# BlueTooth_BM20_Breakout.net
KiCad netlist of a schematic drawn in EAGLE
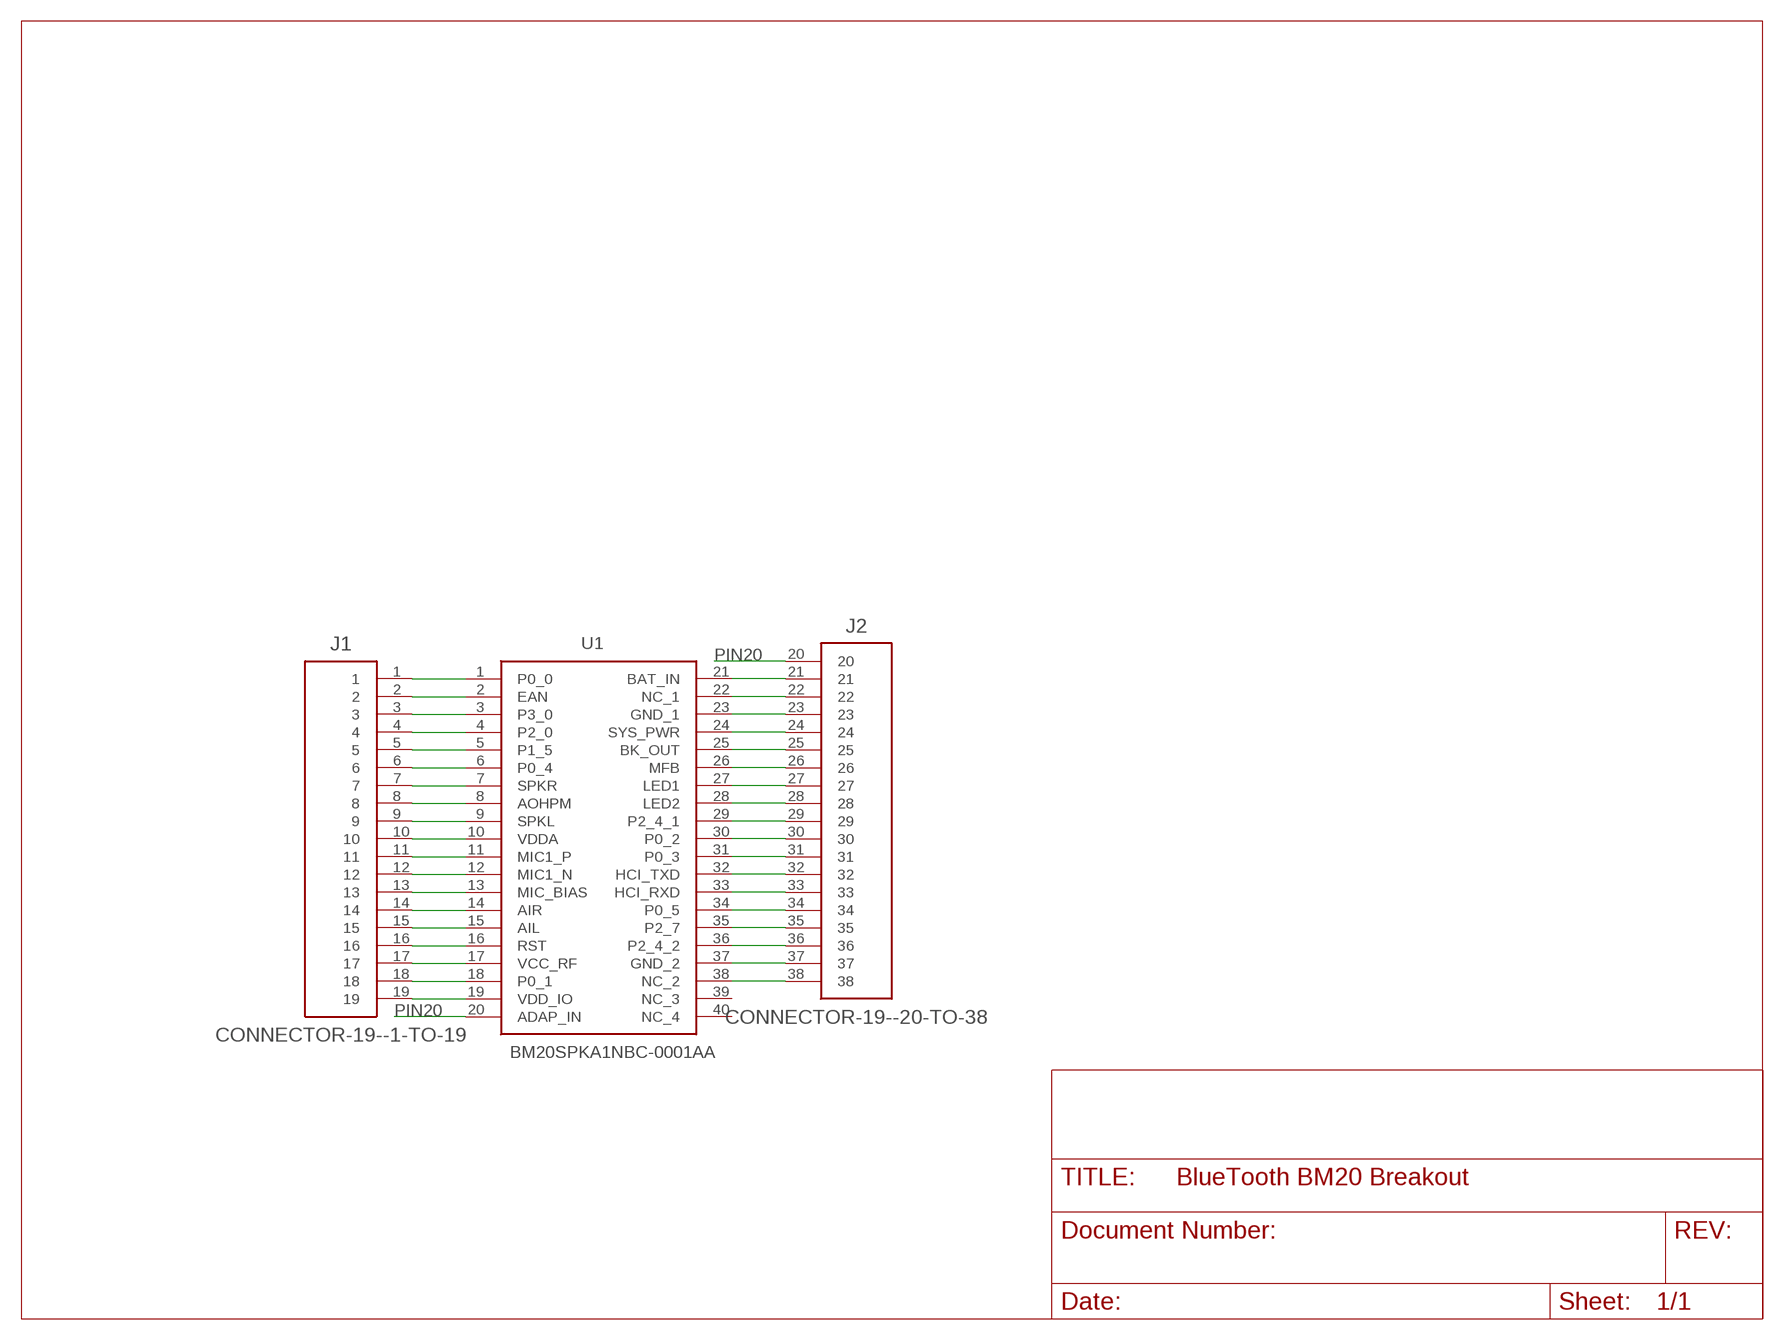
[diagram p0: schematic, sheet 1]

(export (version "E")
  (design (tool "Eeschema 10.0.6"))
  (components
    (comp (ref "J1")
      (value "CONNECTOR-19--1-TO-19")
      (footprint "eagle-import:ESQ-119-XX-XX-S")
      (libsource (lib "eagle-import") (part "CONNECTOR-19--1-TO-19"))
    )
    (comp (ref "J2")
      (value "CONNECTOR-19--20-TO-38")
      (footprint "eagle-import:ESQ-119-XX-XX-S--PIN-1-ROUND")
      (libsource (lib "eagle-import") (part "CONNECTOR-19--20-TO-38"))
    )
    (comp (ref "U1")
      (value "BM20SPKA1NBC-0001AA")
      (footprint "eagle-import:BM20SPKA1NBC0001AA")
      (fields (field (name "MOUSER_PART_NUMBER") "579-SPKA1NBC-0001AA"))
      (libsource (lib "eagle-import") (part "BM20SPKA1NBC-0001AA"))
    )
  )
  (nets
    (net (code "1") (name "/PIN20") (class "Default")
      (node (ref "J2") (pin "20") (pinfunction "20_20") (pintype "bidirectional"))
      (node (ref "U1") (pin "20") (pinfunction "ADAP_IN_20") (pintype "bidirectional"))
    )
    (net (code "2") (name "Net-(U1-AIL)") (class "Default")
      (node (ref "J1") (pin "15") (pinfunction "15_15") (pintype "bidirectional"))
      (node (ref "U1") (pin "15") (pinfunction "AIL_15") (pintype "bidirectional"))
    )
    (net (code "3") (name "Net-(U1-AIR)") (class "Default")
      (node (ref "J1") (pin "14") (pinfunction "14_14") (pintype "bidirectional"))
      (node (ref "U1") (pin "14") (pinfunction "AIR_14") (pintype "bidirectional"))
    )
    (net (code "4") (name "Net-(U1-AOHPM)") (class "Default")
      (node (ref "J1") (pin "8") (pinfunction "8_8") (pintype "bidirectional"))
      (node (ref "U1") (pin "8") (pinfunction "AOHPM_8") (pintype "bidirectional"))
    )
    (net (code "5") (name "Net-(U1-BAT_IN)") (class "Default")
      (node (ref "J2") (pin "21") (pinfunction "21_21") (pintype "bidirectional"))
      (node (ref "U1") (pin "21") (pinfunction "BAT_IN_21") (pintype "bidirectional"))
    )
    (net (code "6") (name "Net-(U1-BK_OUT)") (class "Default")
      (node (ref "J2") (pin "25") (pinfunction "25_25") (pintype "bidirectional"))
      (node (ref "U1") (pin "25") (pinfunction "BK_OUT_25") (pintype "bidirectional"))
    )
    (net (code "7") (name "Net-(U1-EAN)") (class "Default")
      (node (ref "J1") (pin "2") (pinfunction "2_2") (pintype "bidirectional"))
      (node (ref "U1") (pin "2") (pinfunction "EAN_2") (pintype "bidirectional"))
    )
    (net (code "8") (name "Net-(U1-GND_1)") (class "Default")
      (node (ref "J2") (pin "23") (pinfunction "23_23") (pintype "bidirectional"))
      (node (ref "U1") (pin "23") (pinfunction "GND_1_23") (pintype "bidirectional"))
    )
    (net (code "9") (name "Net-(U1-GND_2)") (class "Default")
      (node (ref "J2") (pin "37") (pinfunction "37_37") (pintype "bidirectional"))
      (node (ref "U1") (pin "37") (pinfunction "GND_2_37") (pintype "bidirectional"))
    )
    (net (code "10") (name "Net-(U1-HCI_RXD)") (class "Default")
      (node (ref "J2") (pin "33") (pinfunction "33_33") (pintype "bidirectional"))
      (node (ref "U1") (pin "33") (pinfunction "HCI_RXD_33") (pintype "bidirectional"))
    )
    (net (code "11") (name "Net-(U1-HCI_TXD)") (class "Default")
      (node (ref "J2") (pin "32") (pinfunction "32_32") (pintype "bidirectional"))
      (node (ref "U1") (pin "32") (pinfunction "HCI_TXD_32") (pintype "bidirectional"))
    )
    (net (code "12") (name "Net-(U1-LED1)") (class "Default")
      (node (ref "J2") (pin "27") (pinfunction "27_27") (pintype "bidirectional"))
      (node (ref "U1") (pin "27") (pinfunction "LED1_27") (pintype "bidirectional"))
    )
    (net (code "13") (name "Net-(U1-LED2)") (class "Default")
      (node (ref "J2") (pin "28") (pinfunction "28_28") (pintype "bidirectional"))
      (node (ref "U1") (pin "28") (pinfunction "LED2_28") (pintype "bidirectional"))
    )
    (net (code "14") (name "Net-(U1-MFB)") (class "Default")
      (node (ref "J2") (pin "26") (pinfunction "26_26") (pintype "bidirectional"))
      (node (ref "U1") (pin "26") (pinfunction "MFB_26") (pintype "bidirectional"))
    )
    (net (code "15") (name "Net-(U1-MIC1_N)") (class "Default")
      (node (ref "J1") (pin "12") (pinfunction "12_12") (pintype "bidirectional"))
      (node (ref "U1") (pin "12") (pinfunction "MIC1_N_12") (pintype "bidirectional"))
    )
    (net (code "16") (name "Net-(U1-MIC1_P)") (class "Default")
      (node (ref "J1") (pin "11") (pinfunction "11_11") (pintype "bidirectional"))
      (node (ref "U1") (pin "11") (pinfunction "MIC1_P_11") (pintype "bidirectional"))
    )
    (net (code "17") (name "Net-(U1-MIC_BIAS)") (class "Default")
      (node (ref "J1") (pin "13") (pinfunction "13_13") (pintype "bidirectional"))
      (node (ref "U1") (pin "13") (pinfunction "MIC_BIAS_13") (pintype "bidirectional"))
    )
    (net (code "18") (name "Net-(U1-NC_1)") (class "Default")
      (node (ref "J2") (pin "22") (pinfunction "22_22") (pintype "bidirectional"))
      (node (ref "U1") (pin "22") (pinfunction "NC_1_22") (pintype "bidirectional"))
    )
    (net (code "19") (name "Net-(U1-NC_2)") (class "Default")
      (node (ref "J2") (pin "38") (pinfunction "38_38") (pintype "bidirectional"))
      (node (ref "U1") (pin "38") (pinfunction "NC_2_38") (pintype "bidirectional"))
    )
    (net (code "20") (name "Net-(U1-P0_0)") (class "Default")
      (node (ref "J1") (pin "1") (pinfunction "1_1") (pintype "bidirectional"))
      (node (ref "U1") (pin "1") (pinfunction "P0_0_1") (pintype "bidirectional"))
    )
    (net (code "21") (name "Net-(U1-P0_1)") (class "Default")
      (node (ref "J1") (pin "18") (pinfunction "18_18") (pintype "bidirectional"))
      (node (ref "U1") (pin "18") (pinfunction "P0_1_18") (pintype "bidirectional"))
    )
    (net (code "22") (name "Net-(U1-P0_2)") (class "Default")
      (node (ref "J2") (pin "30") (pinfunction "30_30") (pintype "bidirectional"))
      (node (ref "U1") (pin "30") (pinfunction "P0_2_30") (pintype "bidirectional"))
    )
    (net (code "23") (name "Net-(U1-P0_3)") (class "Default")
      (node (ref "J2") (pin "31") (pinfunction "31_31") (pintype "bidirectional"))
      (node (ref "U1") (pin "31") (pinfunction "P0_3_31") (pintype "bidirectional"))
    )
    (net (code "24") (name "Net-(U1-P0_4)") (class "Default")
      (node (ref "J1") (pin "6") (pinfunction "6_6") (pintype "bidirectional"))
      (node (ref "U1") (pin "6") (pinfunction "P0_4_6") (pintype "bidirectional"))
    )
    (net (code "25") (name "Net-(U1-P0_5)") (class "Default")
      (node (ref "J2") (pin "34") (pinfunction "34_34") (pintype "bidirectional"))
      (node (ref "U1") (pin "34") (pinfunction "P0_5_34") (pintype "bidirectional"))
    )
    (net (code "26") (name "Net-(U1-P1_5)") (class "Default")
      (node (ref "J1") (pin "5") (pinfunction "5_5") (pintype "bidirectional"))
      (node (ref "U1") (pin "5") (pinfunction "P1_5_5") (pintype "bidirectional"))
    )
    (net (code "27") (name "Net-(U1-P2_0)") (class "Default")
      (node (ref "J1") (pin "4") (pinfunction "4_4") (pintype "bidirectional"))
      (node (ref "U1") (pin "4") (pinfunction "P2_0_4") (pintype "bidirectional"))
    )
    (net (code "28") (name "Net-(U1-P2_4_1)") (class "Default")
      (node (ref "J2") (pin "29") (pinfunction "29_29") (pintype "bidirectional"))
      (node (ref "U1") (pin "29") (pinfunction "P2_4_1_29") (pintype "bidirectional"))
    )
    (net (code "29") (name "Net-(U1-P2_4_2)") (class "Default")
      (node (ref "J2") (pin "36") (pinfunction "36_36") (pintype "bidirectional"))
      (node (ref "U1") (pin "36") (pinfunction "P2_4_2_36") (pintype "bidirectional"))
    )
    (net (code "30") (name "Net-(U1-P2_7)") (class "Default")
      (node (ref "J2") (pin "35") (pinfunction "35_35") (pintype "bidirectional"))
      (node (ref "U1") (pin "35") (pinfunction "P2_7_35") (pintype "bidirectional"))
    )
    (net (code "31") (name "Net-(U1-P3_0)") (class "Default")
      (node (ref "J1") (pin "3") (pinfunction "3_3") (pintype "bidirectional"))
      (node (ref "U1") (pin "3") (pinfunction "P3_0_3") (pintype "bidirectional"))
    )
    (net (code "32") (name "Net-(U1-RST)") (class "Default")
      (node (ref "J1") (pin "16") (pinfunction "16_16") (pintype "bidirectional"))
      (node (ref "U1") (pin "16") (pinfunction "RST_16") (pintype "bidirectional"))
    )
    (net (code "33") (name "Net-(U1-SPKL)") (class "Default")
      (node (ref "J1") (pin "9") (pinfunction "9_9") (pintype "bidirectional"))
      (node (ref "U1") (pin "9") (pinfunction "SPKL_9") (pintype "bidirectional"))
    )
    (net (code "34") (name "Net-(U1-SPKR)") (class "Default")
      (node (ref "J1") (pin "7") (pinfunction "7_7") (pintype "bidirectional"))
      (node (ref "U1") (pin "7") (pinfunction "SPKR_7") (pintype "bidirectional"))
    )
    (net (code "35") (name "Net-(U1-SYS_PWR)") (class "Default")
      (node (ref "J2") (pin "24") (pinfunction "24_24") (pintype "bidirectional"))
      (node (ref "U1") (pin "24") (pinfunction "SYS_PWR_24") (pintype "bidirectional"))
    )
    (net (code "36") (name "Net-(U1-VCC_RF)") (class "Default")
      (node (ref "J1") (pin "17") (pinfunction "17_17") (pintype "bidirectional"))
      (node (ref "U1") (pin "17") (pinfunction "VCC_RF_17") (pintype "bidirectional"))
    )
    (net (code "37") (name "Net-(U1-VDDA)") (class "Default")
      (node (ref "J1") (pin "10") (pinfunction "10_10") (pintype "bidirectional"))
      (node (ref "U1") (pin "10") (pinfunction "VDDA_10") (pintype "bidirectional"))
    )
    (net (code "38") (name "Net-(U1-VDD_IO)") (class "Default")
      (node (ref "J1") (pin "19") (pinfunction "19_19") (pintype "bidirectional"))
      (node (ref "U1") (pin "19") (pinfunction "VDD_IO_19") (pintype "bidirectional"))
    )
    (net (code "39") (name "unconnected-(U1-NC_3-Pad39)") (class "Default")
      (node (ref "U1") (pin "39") (pinfunction "NC_3_39") (pintype "bidirectional"))
    )
    (net (code "40") (name "unconnected-(U1-NC_4-Pad40)") (class "Default")
      (node (ref "U1") (pin "40") (pinfunction "NC_4_40") (pintype "bidirectional"))
    )
  )
)
